# Skema_IO.net
KiCad netlist of a schematic drawn in Altium Designer
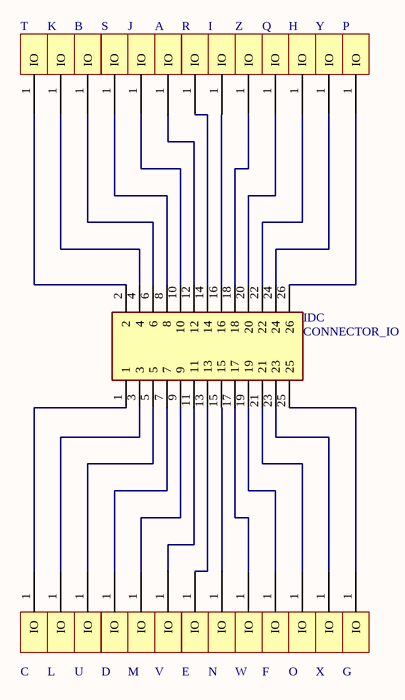
[diagram p0: Skema IO.SchDoc]

(export (version "E")
  (design (tool "Eeschema 10.0.6"))
  (components
    (comp (ref "A")
      (value "Female_Connector_Banana")
      (footprint "F_Banana")
      (libsource (lib "SamacSys") (part "Female_Connector_Banana"))
    )
    (comp (ref "B")
      (value "Female_Connector_Banana")
      (footprint "F_Banana")
      (libsource (lib "SamacSys") (part "Female_Connector_Banana"))
    )
    (comp (ref "C")
      (value "Female_Connector_Banana")
      (footprint "F_Banana")
      (libsource (lib "") (part "Female_Connector_Banana_1"))
    )
    (comp (ref "D")
      (value "Female_Connector_Banana")
      (footprint "F_Banana")
      (libsource (lib "") (part "Female_Connector_Banana_1"))
    )
    (comp (ref "E")
      (value "Female_Connector_Banana")
      (footprint "F_Banana")
      (libsource (lib "") (part "Female_Connector_Banana_1"))
    )
    (comp (ref "F")
      (value "Female_Connector_Banana")
      (footprint "F_Banana")
      (libsource (lib "") (part "Female_Connector_Banana_1"))
    )
    (comp (ref "G")
      (value "Female_Connector_Banana")
      (footprint "F_Banana")
      (libsource (lib "") (part "Female_Connector_Banana_1"))
    )
    (comp (ref "H")
      (value "Female_Connector_Banana")
      (footprint "F_Banana")
      (libsource (lib "SamacSys") (part "Female_Connector_Banana"))
    )
    (comp (ref "I")
      (value "Female_Connector_Banana")
      (footprint "F_Banana")
      (libsource (lib "SamacSys") (part "Female_Connector_Banana"))
    )
    (comp (ref "IDC")
      (value "CONNECTOR_IO")
      (footprint "SamacSys:SHDRRA26W62P254_2X13_4023X957X920P")
      (description "Connector")
      (fields
        (field (name "MANUFACTURER_PART_NUMBER") "75867-105LF")
        (field (name "MOUSER PART NUMBER") "649-75867-105LF")
      )
      (libsource (lib "SamacSys") (part "CONNECTOR_IO"))
    )
    (comp (ref "J")
      (value "Female_Connector_Banana")
      (footprint "F_Banana")
      (libsource (lib "SamacSys") (part "Female_Connector_Banana"))
    )
    (comp (ref "K")
      (value "Female_Connector_Banana")
      (footprint "F_Banana")
      (libsource (lib "SamacSys") (part "Female_Connector_Banana"))
    )
    (comp (ref "L")
      (value "Female_Connector_Banana")
      (footprint "F_Banana")
      (libsource (lib "") (part "Female_Connector_Banana_1"))
    )
    (comp (ref "M")
      (value "Female_Connector_Banana")
      (footprint "F_Banana")
      (libsource (lib "") (part "Female_Connector_Banana_1"))
    )
    (comp (ref "N")
      (value "Female_Connector_Banana")
      (footprint "F_Banana")
      (libsource (lib "") (part "Female_Connector_Banana_1"))
    )
    (comp (ref "O")
      (value "Female_Connector_Banana")
      (footprint "F_Banana")
      (libsource (lib "") (part "Female_Connector_Banana_1"))
    )
    (comp (ref "P")
      (value "Female_Connector_Banana")
      (footprint "F_Banana")
      (libsource (lib "SamacSys") (part "Female_Connector_Banana"))
    )
    (comp (ref "Q")
      (value "Female_Connector_Banana")
      (footprint "F_Banana")
      (libsource (lib "SamacSys") (part "Female_Connector_Banana"))
    )
    (comp (ref "R")
      (value "Female_Connector_Banana")
      (footprint "F_Banana")
      (libsource (lib "SamacSys") (part "Female_Connector_Banana"))
    )
    (comp (ref "S")
      (value "Female_Connector_Banana")
      (footprint "F_Banana")
      (libsource (lib "SamacSys") (part "Female_Connector_Banana"))
    )
    (comp (ref "T")
      (value "Female_Connector_Banana")
      (footprint "F_Banana")
      (libsource (lib "SamacSys") (part "Female_Connector_Banana"))
    )
    (comp (ref "U")
      (value "Female_Connector_Banana")
      (footprint "F_Banana")
      (libsource (lib "") (part "Female_Connector_Banana_1"))
    )
    (comp (ref "V")
      (value "Female_Connector_Banana")
      (footprint "F_Banana")
      (libsource (lib "") (part "Female_Connector_Banana_1"))
    )
    (comp (ref "W")
      (value "Female_Connector_Banana")
      (footprint "F_Banana")
      (libsource (lib "") (part "Female_Connector_Banana_1"))
    )
    (comp (ref "X")
      (value "Female_Connector_Banana")
      (footprint "F_Banana")
      (libsource (lib "") (part "Female_Connector_Banana_1"))
    )
    (comp (ref "Y")
      (value "Female_Connector_Banana")
      (footprint "F_Banana")
      (libsource (lib "SamacSys") (part "Female_Connector_Banana"))
    )
    (comp (ref "Z")
      (value "Female_Connector_Banana")
      (footprint "F_Banana")
      (libsource (lib "SamacSys") (part "Female_Connector_Banana"))
    )
  )
  (nets
    (net (code "1") (name "Net-(A-IO)") (class "Default")
      (node (ref "A") (pin "1") (pinfunction "IO_1") (pintype "passive"))
      (node (ref "IDC") (pin "12") (pinfunction "12_12") (pintype "passive"))
    )
    (net (code "2") (name "Net-(B-IO)") (class "Default")
      (node (ref "B") (pin "1") (pinfunction "IO_1") (pintype "passive"))
      (node (ref "IDC") (pin "6") (pinfunction "6_6") (pintype "passive"))
    )
    (net (code "3") (name "Net-(C-IO)") (class "Default")
      (node (ref "C") (pin "1") (pinfunction "IO_1") (pintype "passive"))
      (node (ref "IDC") (pin "1") (pinfunction "1_1") (pintype "passive"))
    )
    (net (code "4") (name "Net-(D-IO)") (class "Default")
      (node (ref "D") (pin "1") (pinfunction "IO_1") (pintype "passive"))
      (node (ref "IDC") (pin "7") (pinfunction "7_7") (pintype "passive"))
    )
    (net (code "5") (name "Net-(E-IO)") (class "Default")
      (node (ref "E") (pin "1") (pinfunction "IO_1") (pintype "passive"))
      (node (ref "IDC") (pin "13") (pinfunction "13_13") (pintype "passive"))
    )
    (net (code "6") (name "Net-(F-IO)") (class "Default")
      (node (ref "F") (pin "1") (pinfunction "IO_1") (pintype "passive"))
      (node (ref "IDC") (pin "19") (pinfunction "19_19") (pintype "passive"))
    )
    (net (code "7") (name "Net-(G-IO)") (class "Default")
      (node (ref "G") (pin "1") (pinfunction "IO_1") (pintype "passive"))
      (node (ref "IDC") (pin "25") (pinfunction "25_25") (pintype "passive"))
    )
    (net (code "8") (name "Net-(H-IO)") (class "Default")
      (node (ref "H") (pin "1") (pinfunction "IO_1") (pintype "passive"))
      (node (ref "IDC") (pin "22") (pinfunction "22_22") (pintype "passive"))
    )
    (net (code "9") (name "Net-(I-IO)") (class "Default")
      (node (ref "I") (pin "1") (pinfunction "IO_1") (pintype "passive"))
      (node (ref "IDC") (pin "16") (pinfunction "16_16") (pintype "passive"))
    )
    (net (code "10") (name "Net-(J-IO)") (class "Default")
      (node (ref "IDC") (pin "10") (pinfunction "10_10") (pintype "passive"))
      (node (ref "J") (pin "1") (pinfunction "IO_1") (pintype "passive"))
    )
    (net (code "11") (name "Net-(K-IO)") (class "Default")
      (node (ref "IDC") (pin "4") (pinfunction "4_4") (pintype "passive"))
      (node (ref "K") (pin "1") (pinfunction "IO_1") (pintype "passive"))
    )
    (net (code "12") (name "Net-(L-IO)") (class "Default")
      (node (ref "IDC") (pin "3") (pinfunction "3_3") (pintype "passive"))
      (node (ref "L") (pin "1") (pinfunction "IO_1") (pintype "passive"))
    )
    (net (code "13") (name "Net-(M-IO)") (class "Default")
      (node (ref "IDC") (pin "9") (pinfunction "9_9") (pintype "passive"))
      (node (ref "M") (pin "1") (pinfunction "IO_1") (pintype "passive"))
    )
    (net (code "14") (name "Net-(N-IO)") (class "Default")
      (node (ref "IDC") (pin "15") (pinfunction "15_15") (pintype "passive"))
      (node (ref "N") (pin "1") (pinfunction "IO_1") (pintype "passive"))
    )
    (net (code "15") (name "Net-(O-IO)") (class "Default")
      (node (ref "IDC") (pin "21") (pinfunction "21_21") (pintype "passive"))
      (node (ref "O") (pin "1") (pinfunction "IO_1") (pintype "passive"))
    )
    (net (code "16") (name "Net-(P-IO)") (class "Default")
      (node (ref "IDC") (pin "26") (pinfunction "26_26") (pintype "passive"))
      (node (ref "P") (pin "1") (pinfunction "IO_1") (pintype "passive"))
    )
    (net (code "17") (name "Net-(Q-IO)") (class "Default")
      (node (ref "IDC") (pin "20") (pinfunction "20_20") (pintype "passive"))
      (node (ref "Q") (pin "1") (pinfunction "IO_1") (pintype "passive"))
    )
    (net (code "18") (name "Net-(R-IO)") (class "Default")
      (node (ref "IDC") (pin "14") (pinfunction "14_14") (pintype "passive"))
      (node (ref "R") (pin "1") (pinfunction "IO_1") (pintype "passive"))
    )
    (net (code "19") (name "Net-(S-IO)") (class "Default")
      (node (ref "IDC") (pin "8") (pinfunction "8_8") (pintype "passive"))
      (node (ref "S") (pin "1") (pinfunction "IO_1") (pintype "passive"))
    )
    (net (code "20") (name "Net-(T-IO)") (class "Default")
      (node (ref "IDC") (pin "2") (pinfunction "2_2") (pintype "passive"))
      (node (ref "T") (pin "1") (pinfunction "IO_1") (pintype "passive"))
    )
    (net (code "21") (name "Net-(U-IO)") (class "Default")
      (node (ref "IDC") (pin "5") (pinfunction "5_5") (pintype "passive"))
      (node (ref "U") (pin "1") (pinfunction "IO_1") (pintype "passive"))
    )
    (net (code "22") (name "Net-(V-IO)") (class "Default")
      (node (ref "IDC") (pin "11") (pinfunction "11_11") (pintype "passive"))
      (node (ref "V") (pin "1") (pinfunction "IO_1") (pintype "passive"))
    )
    (net (code "23") (name "Net-(W-IO)") (class "Default")
      (node (ref "IDC") (pin "17") (pinfunction "17_17") (pintype "passive"))
      (node (ref "W") (pin "1") (pinfunction "IO_1") (pintype "passive"))
    )
    (net (code "24") (name "Net-(X-IO)") (class "Default")
      (node (ref "IDC") (pin "23") (pinfunction "23_23") (pintype "passive"))
      (node (ref "X") (pin "1") (pinfunction "IO_1") (pintype "passive"))
    )
    (net (code "25") (name "Net-(Y-IO)") (class "Default")
      (node (ref "IDC") (pin "24") (pinfunction "24_24") (pintype "passive"))
      (node (ref "Y") (pin "1") (pinfunction "IO_1") (pintype "passive"))
    )
    (net (code "26") (name "Net-(Z-IO)") (class "Default")
      (node (ref "IDC") (pin "18") (pinfunction "18_18") (pintype "passive"))
      (node (ref "Z") (pin "1") (pinfunction "IO_1") (pintype "passive"))
    )
  )
)
